# spoofer.net
KiCad netlist of a schematic drawn in Altium Designer
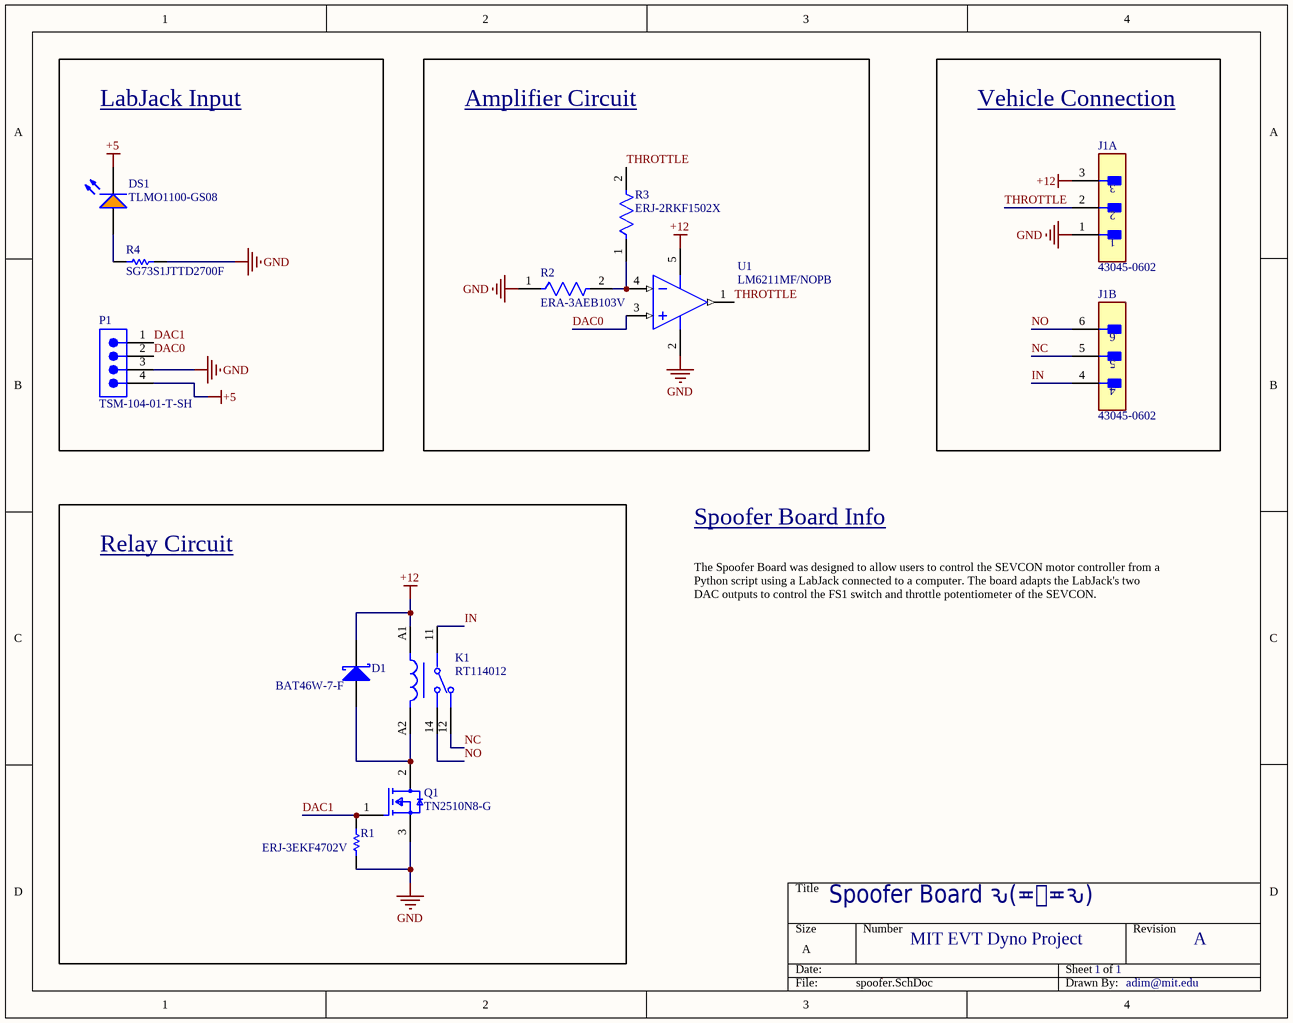
[diagram p0: spoofer.SchDoc]

(export (version "E")
  (design (tool "Eeschema 10.0.6"))
  (components
    (comp (ref "D1")
      (value "BAT46W-7-F")
      (footprint "DIOD-SOD-123-2_V")
      (description "Surface Mount Schottky Barrier Diode, 100 V, -55 to 125 degC, 2-Pin SOD123, RoHS, Tape and Reel")
      (fields (field (name "MANUFACTURER") "Diodes Inc"))
      (libsource (lib "Altium Content Vault") (part "DIOD-DSKY-A1K2-2"))
    )
    (comp (ref "DS1")
      (value "TLMO1100-GS08")
      (footprint "VISH-TLMX1100-2_V")
      (description "Orange LED, 20 mA, 2.1 V, -40 to 100 degC, 2-Pin SMD (0603), RoHS, Tape and Reel")
      (libsource (lib "Altium Content Vault") (part "LED-ORANGE-AK-2"))
    )
    (comp (ref "J1")
      (value "43045-0602")
      (footprint "FP-43045-0602-MFG")
      (description "CONN HEADER R/A 6POS 3MM")
      (libsource (lib "Altium Content Vault") (part "7bb5f7ddfb2bec276e641070710345c"))
    )
    (comp (ref "K1")
      (value "RT114012")
      (footprint "FP-RT114012-MFG")
      (description "RELAY GEN PURPOSE SPDT 12A 12V")
      (fields
        (field (name "OCTOPART") "https://octopart.com/rt114012-te+connectivity-39636422")
        (field (name "MANUFACTURER") "TE Connectivity")
      )
      (libsource (lib "Altium Content Vault") (part "073c63e877000fb1b84f95b80705c0f"))
    )
    (comp (ref "P1")
      (value "TSM-104-01-T-SH")
      (footprint "SMTC-TSM-104-01-X-SH")
      (fields (field (name "MANUFACTURER") "Samtec"))
      (libsource (lib "Altium Content Vault") (part "SMTC-TSM-104-01-X-SH"))
    )
    (comp (ref "Q1")
      (value "TN2510N8-G")
      (footprint "FP-TN2510N8-G-IPC_C")
      (description "MOSFET N-CH 100V 730MA TO243AA")
      (libsource (lib "Altium Content Vault") (part "0c230b6be11ab2f8d79771084c6aa09"))
    )
    (comp (ref "R1")
      (value "ERJ-3EKF4702V")
      (footprint "RESC1608X55X30NL15T15")
      (description "Chip Resistor, 47 KOhm, +/- 1%, 0.1 W, -55 to 155 degC, 0603 (1608 Metric), RoHS, Tape and Reel")
      (libsource (lib "Altium Content Vault") (part "RES-2"))
    )
    (comp (ref "R2")
      (value "ERA-3AEB103V")
      (footprint "FP-ERA3A-IPC_C")
      (description "RES SMD 10K OHM 0.1% 1/10W 0603")
      (fields (field (name "TOLERANCE") "0.1%"))
      (libsource (lib "Altium Content Vault") (part "4e5f8b3dd332802e91518312df5df73"))
    )
    (comp (ref "R3")
      (value "ERJ-2RKF1502X")
      (footprint "FP-ERJ2R-MFG")
      (description "RES SMD 15K OHM 1% 1/10W 0402")
      (fields
        (field (name "TOLERANCE") "1%")
        (field (name "OCTOPART") "https://octopart.com/erj-2rkf1502x-panasonic-55404985")
      )
      (libsource (lib "Altium Content Vault") (part "1029c3af85768c4190bb7ad29bc67b5"))
    )
    (comp (ref "R4")
      (value "SG73S1JTTD2700F")
      (footprint "RESC1608X55X30ML20T10")
      (fields (field (name "MANUFACTURER") "KOA Speer"))
      (libsource (lib "Altium Content Vault") (part "RES"))
    )
    (comp (ref "U1")
      (value "LM6211MF/NOPB")
      (footprint "DBV0005A_L")
      (description "Low Noise, RRO Operational Amplifier with CMOS Input and 24V Operation, 5-pin SOT-23, Pb-Free")
      (fields (field (name "MANUFACTURER") "Texas Instruments"))
      (libsource (lib "Altium Content Vault") (part "AMP-OPA-LM6211-5"))
    )
  )
  (nets
    (net (code "1") (name "+5") (class "Default")
      (node (ref "DS1") (pin "2") (pinfunction "K_2") (pintype "passive"))
      (node (ref "P1") (pin "4") (pinfunction "4_4") (pintype "passive"))
    )
    (net (code "2") (name "+12") (class "Default")
      (node (ref "D1") (pin "2") (pinfunction "K_2") (pintype "passive"))
      (node (ref "J1") (pin "3") (pinfunction "3_3") (pintype "passive"))
      (node (ref "K1") (pin "A1") (pinfunction "A1_A1") (pintype "passive"))
      (node (ref "U1") (pin "5") (pinfunction "V+_5") (pintype "power_in"))
    )
    (net (code "3") (name "/DAC0") (class "Default")
      (node (ref "P1") (pin "2") (pinfunction "2_2") (pintype "passive"))
      (node (ref "U1") (pin "3") (pinfunction "IN+_3") (pintype "input"))
    )
    (net (code "4") (name "/DAC1") (class "Default")
      (node (ref "P1") (pin "1") (pinfunction "1_1") (pintype "passive"))
      (node (ref "Q1") (pin "1") (pinfunction "GATE_1") (pintype "passive"))
      (node (ref "R1") (pin "2") (pinfunction "2_2") (pintype "passive"))
    )
    (net (code "5") (name "/IN") (class "Default")
      (node (ref "J1") (pin "4") (pinfunction "4_4") (pintype "passive"))
      (node (ref "K1") (pin "11") (pinfunction "11_11") (pintype "passive"))
    )
    (net (code "6") (name "/NC") (class "Default")
      (node (ref "J1") (pin "5") (pinfunction "5_5") (pintype "passive"))
      (node (ref "K1") (pin "12") (pinfunction "12_12") (pintype "passive"))
    )
    (net (code "7") (name "/NO") (class "Default")
      (node (ref "J1") (pin "6") (pinfunction "6_6") (pintype "passive"))
      (node (ref "K1") (pin "14") (pinfunction "14_14") (pintype "passive"))
    )
    (net (code "8") (name "/THROTTLE") (class "Default")
      (node (ref "J1") (pin "2") (pinfunction "2_2") (pintype "passive"))
      (node (ref "R3") (pin "2") (pinfunction "2_2") (pintype "passive"))
      (node (ref "U1") (pin "1") (pinfunction "VOUT_1") (pintype "output"))
    )
    (net (code "9") (name "GND") (class "Default")
      (node (ref "J1") (pin "1") (pinfunction "1_1") (pintype "passive"))
      (node (ref "P1") (pin "3") (pinfunction "3_3") (pintype "passive"))
      (node (ref "Q1") (pin "3") (pinfunction "SOURCE_3") (pintype "passive"))
      (node (ref "R1") (pin "1") (pinfunction "1_1") (pintype "passive"))
      (node (ref "R2") (pin "1") (pinfunction "1_1") (pintype "passive"))
      (node (ref "R4") (pin "2") (pinfunction "2_2") (pintype "passive"))
      (node (ref "U1") (pin "2") (pinfunction "V-_2") (pintype "power_in"))
    )
    (net (code "10") (name "Net-(D1-A)") (class "Default")
      (node (ref "D1") (pin "1") (pinfunction "A_1") (pintype "passive"))
      (node (ref "K1") (pin "A2") (pinfunction "A2_A2") (pintype "passive"))
      (node (ref "Q1") (pin "2") (pinfunction "DRAIN_2") (pintype "passive"))
    )
    (net (code "11") (name "Net-(DS1-A)") (class "Default")
      (node (ref "DS1") (pin "1") (pinfunction "A_1") (pintype "passive"))
      (node (ref "R4") (pin "1") (pinfunction "1_1") (pintype "passive"))
    )
    (net (code "12") (name "Net-(U1-IN-)") (class "Default")
      (node (ref "R2") (pin "2") (pinfunction "2_2") (pintype "passive"))
      (node (ref "R3") (pin "1") (pinfunction "1_1") (pintype "passive"))
      (node (ref "U1") (pin "4") (pinfunction "IN-_4") (pintype "input"))
    )
  )
)
